# pid_driver.net
KiCad netlist of a schematic drawn in EAGLE
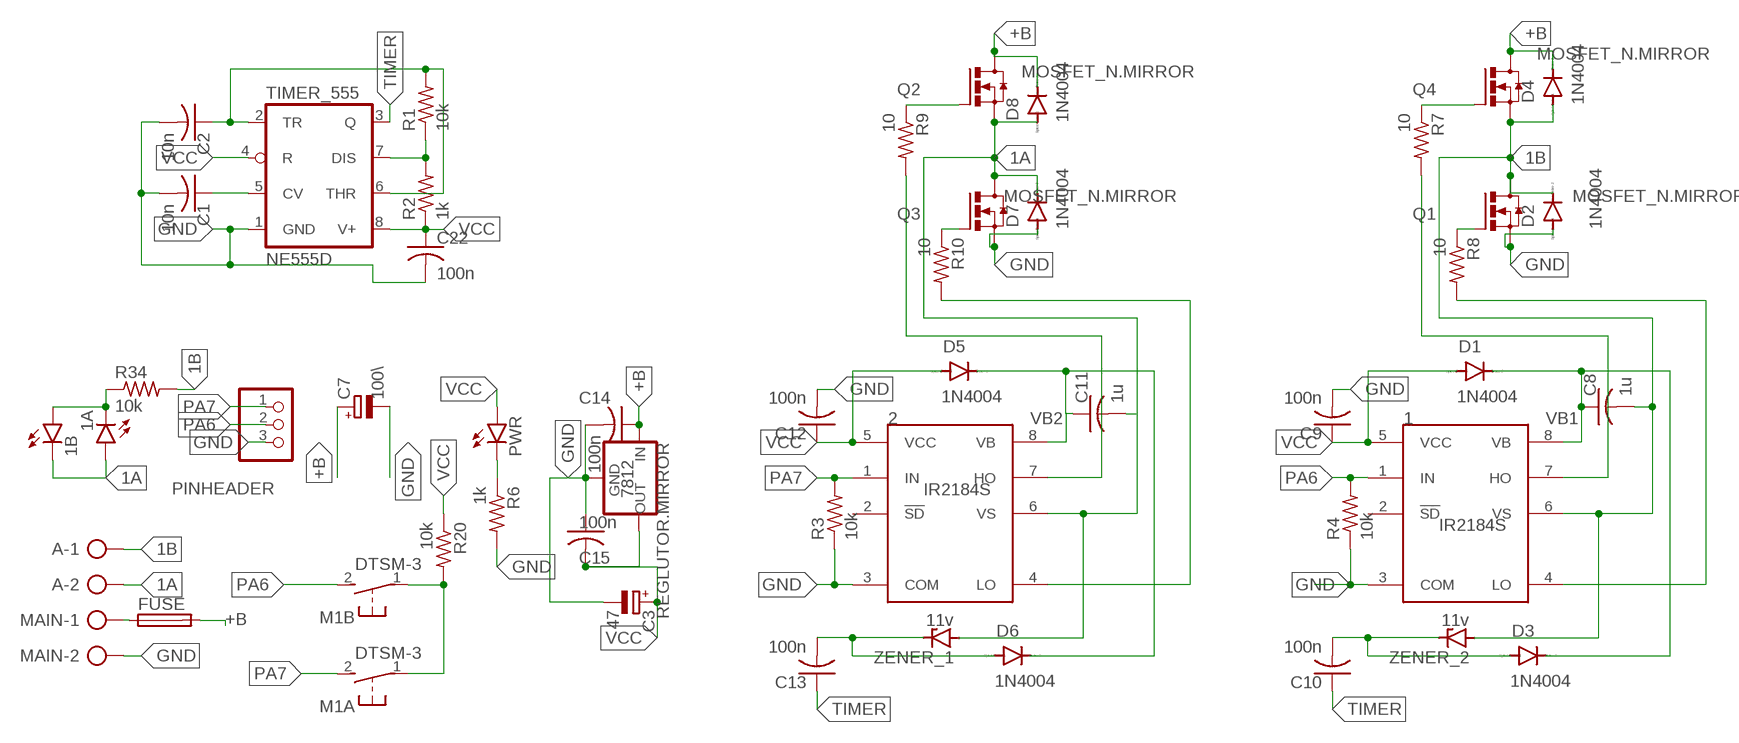
[diagram p0: schematic, sheet 1]
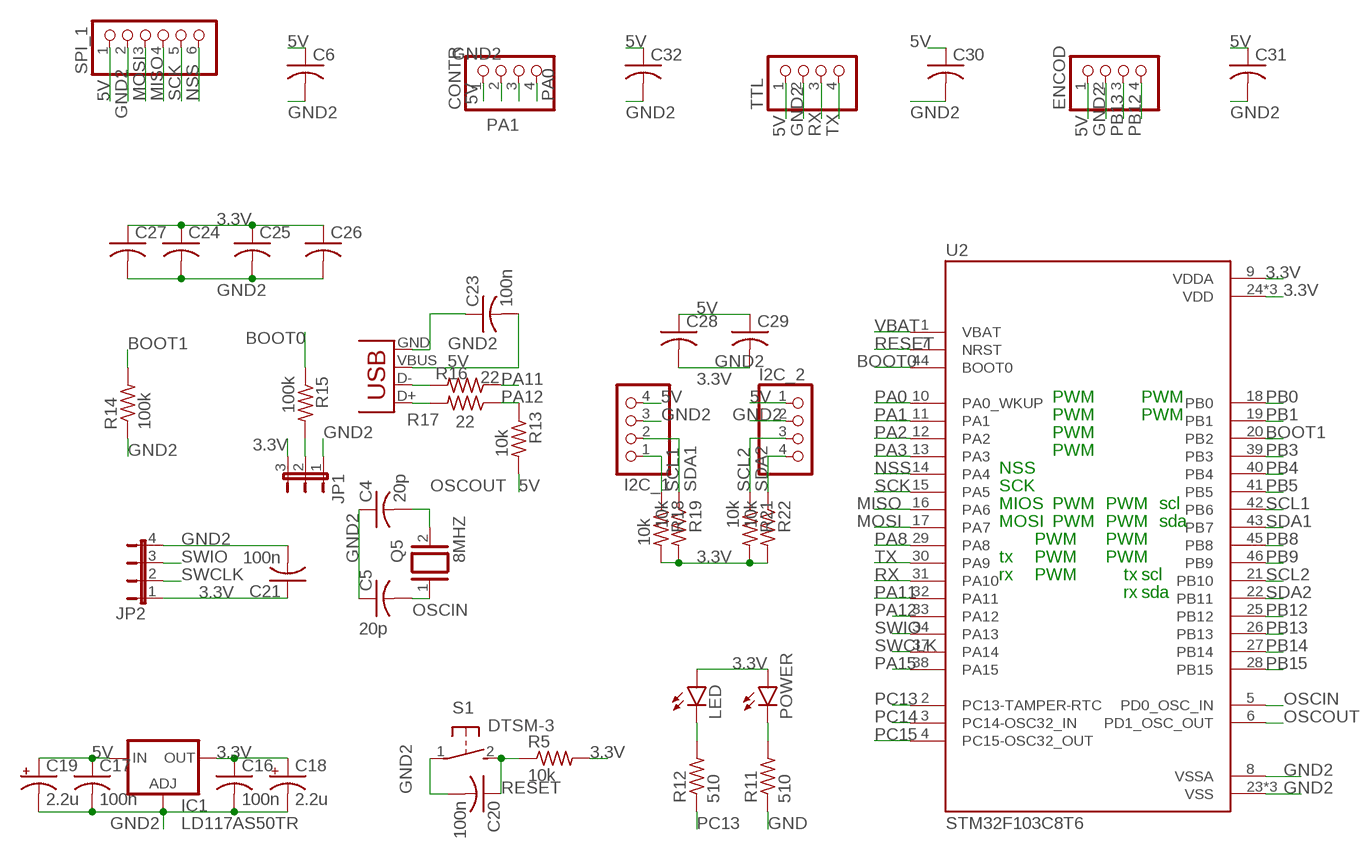
[diagram p1: schematic, sheet 2]

(export (version "E")
  (design (tool "Eeschema 10.0.6"))
  (components
    (comp (ref "1")
      (value "IR2184S")
      (footprint "eagle-import:SO08")
      (libsource (lib "eagle-import") (part "IR2184S"))
    )
    (comp (ref "1A")
      (value "LEDCHIPLED_1206")
      (footprint "eagle-import:CHIPLED_1206")
      (libsource (lib "eagle-import") (part "LEDCHIPLED_1206"))
    )
    (comp (ref "1B")
      (value "LEDCHIPLED_1206")
      (footprint "eagle-import:CHIPLED_1206")
      (libsource (lib "eagle-import") (part "LEDCHIPLED_1206"))
    )
    (comp (ref "2")
      (value "IR2184S")
      (footprint "eagle-import:SO08")
      (libsource (lib "eagle-import") (part "IR2184S"))
    )
    (comp (ref "7812")
      (value "REGLUTOR.MIRROR")
      (footprint "eagle-import:78XXL.MIRROR")
      (libsource (lib "eagle-import") (part "REGLUTOR.MIRROR"))
    )
    (comp (ref "A")
      (value "AK300/22")
      (footprint "eagle-import:XTALRR488W60L1090T465H350B")
      (libsource (lib "eagle-import") (part "AK300/22"))
    )
    (comp (ref "C1")
      (value "10n")
      (footprint "eagle-import:C1206K")
      (libsource (lib "eagle-import") (part "C-USC1206K"))
    )
    (comp (ref "C2")
      (value "10n")
      (footprint "eagle-import:C1206K")
      (libsource (lib "eagle-import") (part "C-USC1206K"))
    )
    (comp (ref "C3")
      (value "47")
      (footprint "eagle-import:E5-10,5")
      (libsource (lib "eagle-import") (part "CPOL-EUE5-10.5"))
    )
    (comp (ref "C7")
      (value "100\\")
      (footprint "eagle-import:E5-10,5")
      (libsource (lib "eagle-import") (part "CPOL-EUE5-10.5"))
    )
    (comp (ref "C8")
      (value "1u")
      (footprint "eagle-import:C1206K")
      (libsource (lib "eagle-import") (part "C-USC1206K"))
    )
    (comp (ref "C9")
      (value "100n")
      (footprint "eagle-import:C1206K")
      (libsource (lib "eagle-import") (part "C-USC1206K"))
    )
    (comp (ref "C10")
      (value "100n")
      (footprint "eagle-import:C1206K")
      (libsource (lib "eagle-import") (part "C-USC1206K"))
    )
    (comp (ref "C11")
      (value "1u")
      (footprint "eagle-import:C1206K")
      (libsource (lib "eagle-import") (part "C-USC1206K"))
    )
    (comp (ref "C12")
      (value "100n")
      (footprint "eagle-import:C1206K")
      (libsource (lib "eagle-import") (part "C-USC1206K"))
    )
    (comp (ref "C13")
      (value "100n")
      (footprint "eagle-import:C1206K")
      (libsource (lib "eagle-import") (part "C-USC1206K"))
    )
    (comp (ref "C14")
      (value "100n")
      (footprint "eagle-import:C1206K")
      (libsource (lib "eagle-import") (part "C-USC1206K"))
    )
    (comp (ref "C15")
      (value "100n")
      (footprint "eagle-import:C1206K")
      (libsource (lib "eagle-import") (part "C-USC1206K"))
    )
    (comp (ref "C22")
      (value "100n")
      (footprint "eagle-import:C1206K")
      (libsource (lib "eagle-import") (part "C-USC1206K"))
    )
    (comp (ref "D1")
      (value "1N4004")
      (footprint "eagle-import:DO41-10")
      (libsource (lib "eagle-import") (part "1N4004"))
    )
    (comp (ref "D2")
      (value "1N4004")
      (footprint "eagle-import:DO41-10")
      (libsource (lib "eagle-import") (part "1N4004"))
    )
    (comp (ref "D3")
      (value "1N4004")
      (footprint "eagle-import:DO41-10")
      (libsource (lib "eagle-import") (part "1N4004"))
    )
    (comp (ref "D4")
      (value "1N4004")
      (footprint "eagle-import:DO41-10")
      (libsource (lib "eagle-import") (part "1N4004"))
    )
    (comp (ref "D5")
      (value "1N4004")
      (footprint "eagle-import:DO41-10")
      (libsource (lib "eagle-import") (part "1N4004"))
    )
    (comp (ref "D6")
      (value "1N4004")
      (footprint "eagle-import:DO41-10")
      (libsource (lib "eagle-import") (part "1N4004"))
    )
    (comp (ref "D7")
      (value "1N4004")
      (footprint "eagle-import:DO41-10")
      (libsource (lib "eagle-import") (part "1N4004"))
    )
    (comp (ref "D8")
      (value "1N4004")
      (footprint "eagle-import:DO41-10")
      (libsource (lib "eagle-import") (part "1N4004"))
    )
    (comp (ref "FUSE")
      (value "FUSE_HOLDER")
      (footprint "eagle-import:SH22,5A")
      (libsource (lib "eagle-import") (part "FUSE_HOLDER"))
    )
    (comp (ref "M1A")
      (value "DTSM-3")
      (footprint "eagle-import:DTSM-3")
      (libsource (lib "eagle-import") (part "DTSM-3"))
    )
    (comp (ref "M1B")
      (value "DTSM-3")
      (footprint "eagle-import:DTSM-3")
      (libsource (lib "eagle-import") (part "DTSM-3"))
    )
    (comp (ref "MAIN")
      (value "AK300/22")
      (footprint "eagle-import:XTALRR488W60L1090T465H350B")
      (libsource (lib "eagle-import") (part "AK300/22"))
    )
    (comp (ref "PINHEADER")
      (value "PINHD-1X3")
      (footprint "eagle-import:1X03")
      (libsource (lib "eagle-import") (part "PINHD-1X3"))
    )
    (comp (ref "PWR")
      (value "LEDCHIPLED_1206")
      (footprint "eagle-import:CHIPLED_1206")
      (libsource (lib "eagle-import") (part "LEDCHIPLED_1206"))
    )
    (comp (ref "Q1")
      (value "MOSFET_N.MIRROR")
      (footprint "eagle-import:TO220.MIRROR")
      (libsource (lib "eagle-import") (part "MOSFET_N.MIRROR"))
    )
    (comp (ref "Q2")
      (value "MOSFET_N.MIRROR")
      (footprint "eagle-import:TO220.MIRROR")
      (libsource (lib "eagle-import") (part "MOSFET_N.MIRROR"))
    )
    (comp (ref "Q3")
      (value "MOSFET_N.MIRROR")
      (footprint "eagle-import:TO220.MIRROR")
      (libsource (lib "eagle-import") (part "MOSFET_N.MIRROR"))
    )
    (comp (ref "Q4")
      (value "MOSFET_N.MIRROR")
      (footprint "eagle-import:TO220.MIRROR")
      (libsource (lib "eagle-import") (part "MOSFET_N.MIRROR"))
    )
    (comp (ref "R1")
      (value "10k")
      (footprint "eagle-import:M1206")
      (libsource (lib "eagle-import") (part "R-US_M1206"))
    )
    (comp (ref "R2")
      (value "1k")
      (footprint "eagle-import:M1206")
      (libsource (lib "eagle-import") (part "R-US_M1206"))
    )
    (comp (ref "R3")
      (value "10k")
      (footprint "eagle-import:M1206")
      (libsource (lib "eagle-import") (part "R-US_M1206"))
    )
    (comp (ref "R4")
      (value "10k")
      (footprint "eagle-import:M1206")
      (libsource (lib "eagle-import") (part "R-US_M1206"))
    )
    (comp (ref "R6")
      (value "1k")
      (footprint "eagle-import:M1206")
      (libsource (lib "eagle-import") (part "R-US_M1206"))
    )
    (comp (ref "R7")
      (value "10")
      (footprint "eagle-import:M1206")
      (libsource (lib "eagle-import") (part "R-US_M1206"))
    )
    (comp (ref "R8")
      (value "10")
      (footprint "eagle-import:M1206")
      (libsource (lib "eagle-import") (part "R-US_M1206"))
    )
    (comp (ref "R9")
      (value "10")
      (footprint "eagle-import:M1206")
      (libsource (lib "eagle-import") (part "R-US_M1206"))
    )
    (comp (ref "R10")
      (value "10")
      (footprint "eagle-import:M1206")
      (libsource (lib "eagle-import") (part "R-US_M1206"))
    )
    (comp (ref "R20")
      (value "10k")
      (footprint "eagle-import:M1206")
      (libsource (lib "eagle-import") (part "R-US_M1206"))
    )
    (comp (ref "R34")
      (value "10k")
      (footprint "eagle-import:M1206")
      (libsource (lib "eagle-import") (part "R-US_M1206"))
    )
    (comp (ref "TIMER_555")
      (value "NE555D")
      (footprint "eagle-import:SO08")
      (libsource (lib "eagle-import") (part "555DNE"))
    )
    (comp (ref "ZENER_1")
      (value "11v")
      (footprint "eagle-import:SOD81")
      (libsource (lib "eagle-import") (part "BZD23"))
    )
    (comp (ref "ZENER_2")
      (value "11v")
      (footprint "eagle-import:SOD81")
      (libsource (lib "eagle-import") (part "BZD23"))
    )
    (comp (ref "C4")
      (value "20p")
      (footprint "eagle-import:C1206")
      (libsource (lib "eagle-import") (part "C-USC1206"))
    )
    (comp (ref "C5")
      (value "20p")
      (footprint "eagle-import:C1206")
      (libsource (lib "eagle-import") (part "C-USC1206"))
    )
    (comp (ref "C6")
      (value "C-USC1206")
      (footprint "eagle-import:C1206")
      (libsource (lib "eagle-import") (part "C-USC1206"))
    )
    (comp (ref "C16")
      (value "100n")
      (footprint "eagle-import:C1206")
      (libsource (lib "eagle-import") (part "C-USC1206"))
    )
    (comp (ref "C17")
      (value "100n")
      (footprint "eagle-import:C1206")
      (libsource (lib "eagle-import") (part "C-USC1206"))
    )
    (comp (ref "C18")
      (value "2.2u")
      (footprint "eagle-import:E2-5")
      (libsource (lib "eagle-import") (part "CPOL-USE2-5"))
    )
    (comp (ref "C19")
      (value "2.2u")
      (footprint "eagle-import:E2-5")
      (libsource (lib "eagle-import") (part "CPOL-USE2-5"))
    )
    (comp (ref "C20")
      (value "100n")
      (footprint "eagle-import:C1206")
      (libsource (lib "eagle-import") (part "C-USC1206"))
    )
    (comp (ref "C21")
      (value "100n")
      (footprint "eagle-import:C1206")
      (libsource (lib "eagle-import") (part "C-USC1206"))
    )
    (comp (ref "C23")
      (value "100n")
      (footprint "eagle-import:C1206")
      (libsource (lib "eagle-import") (part "C-USC1206"))
    )
    (comp (ref "C24")
      (value "C-USC1206")
      (footprint "eagle-import:C1206")
      (libsource (lib "eagle-import") (part "C-USC1206"))
    )
    (comp (ref "C25")
      (value "C-USC1206")
      (footprint "eagle-import:C1206")
      (libsource (lib "eagle-import") (part "C-USC1206"))
    )
    (comp (ref "C26")
      (value "C-USC1206")
      (footprint "eagle-import:C1206")
      (libsource (lib "eagle-import") (part "C-USC1206"))
    )
    (comp (ref "C27")
      (value "C-USC1206")
      (footprint "eagle-import:C1206")
      (libsource (lib "eagle-import") (part "C-USC1206"))
    )
    (comp (ref "C28")
      (value "C-USC1206")
      (footprint "eagle-import:C1206")
      (libsource (lib "eagle-import") (part "C-USC1206"))
    )
    (comp (ref "C29")
      (value "C-USC1206")
      (footprint "eagle-import:C1206")
      (libsource (lib "eagle-import") (part "C-USC1206"))
    )
    (comp (ref "C30")
      (value "C-USC1206")
      (footprint "eagle-import:C1206")
      (libsource (lib "eagle-import") (part "C-USC1206"))
    )
    (comp (ref "C31")
      (value "C-USC1206")
      (footprint "eagle-import:C1206")
      (libsource (lib "eagle-import") (part "C-USC1206"))
    )
    (comp (ref "C32")
      (value "C-USC1206")
      (footprint "eagle-import:C1206")
      (libsource (lib "eagle-import") (part "C-USC1206"))
    )
    (comp (ref "CONTR")
      (value "PINHD-1X4")
      (footprint "eagle-import:1X04")
      (libsource (lib "eagle-import") (part "PINHD-1X4"))
    )
    (comp (ref "ENCOD")
      (value "PINHD-1X4")
      (footprint "eagle-import:1X04")
      (libsource (lib "eagle-import") (part "PINHD-1X4"))
    )
    (comp (ref "I2C_1")
      (value "PINHD-1X4")
      (footprint "eagle-import:1X04")
      (libsource (lib "eagle-import") (part "pinhead_325_PINHD-1X4"))
    )
    (comp (ref "I2C_2")
      (value "PINHD-1X4")
      (footprint "eagle-import:1X04")
      (libsource (lib "eagle-import") (part "pinhead_325_PINHD-1X4"))
    )
    (comp (ref "IC1")
      (value "LD117AS50TR")
      (footprint "eagle-import:SOT223")
      (libsource (lib "eagle-import") (part "LD117A?S50TR"))
    )
    (comp (ref "JP1")
      (value "JP2E")
      (footprint "eagle-import:JP2")
      (libsource (lib "eagle-import") (part "JP2E"))
    )
    (comp (ref "JP2")
      (value "JP4E")
      (footprint "eagle-import:JP4")
      (libsource (lib "eagle-import") (part "JP4E"))
    )
    (comp (ref "LED")
      (value "LEDCHIPLED_1206")
      (footprint "eagle-import:CHIPLED_1206")
      (libsource (lib "eagle-import") (part "LEDCHIPLED_1206"))
    )
    (comp (ref "POWER")
      (value "LEDCHIPLED_1206")
      (footprint "eagle-import:CHIPLED_1206")
      (libsource (lib "eagle-import") (part "LEDCHIPLED_1206"))
    )
    (comp (ref "Q5")
      (value "8MHZ")
      (footprint "eagle-import:QS")
      (libsource (lib "eagle-import") (part "XTAL/S"))
    )
    (comp (ref "R5")
      (value "10k")
      (footprint "eagle-import:R1206")
      (libsource (lib "eagle-import") (part "R-US_R1206"))
    )
    (comp (ref "R11")
      (value "510")
      (footprint "eagle-import:R1206")
      (libsource (lib "eagle-import") (part "R-US_R1206"))
    )
    (comp (ref "R12")
      (value "510")
      (footprint "eagle-import:R1206")
      (libsource (lib "eagle-import") (part "R-US_R1206"))
    )
    (comp (ref "R13")
      (value "10k")
      (footprint "eagle-import:R1206")
      (libsource (lib "eagle-import") (part "R-US_R1206"))
    )
    (comp (ref "R14")
      (value "100k")
      (footprint "eagle-import:R1206")
      (libsource (lib "eagle-import") (part "R-US_R1206"))
    )
    (comp (ref "R15")
      (value "100k")
      (footprint "eagle-import:R1206")
      (libsource (lib "eagle-import") (part "R-US_R1206"))
    )
    (comp (ref "R16")
      (value "22")
      (footprint "eagle-import:R1206")
      (libsource (lib "eagle-import") (part "R-US_R1206"))
    )
    (comp (ref "R17")
      (value "22")
      (footprint "eagle-import:R1206")
      (libsource (lib "eagle-import") (part "R-US_R1206"))
    )
    (comp (ref "R18")
      (value "10k")
      (footprint "eagle-import:R1206")
      (libsource (lib "eagle-import") (part "R-US_R1206"))
    )
    (comp (ref "R19")
      (value "10k")
      (footprint "eagle-import:R1206")
      (libsource (lib "eagle-import") (part "R-US_R1206"))
    )
    (comp (ref "R21")
      (value "10k")
      (footprint "eagle-import:R1206")
      (libsource (lib "eagle-import") (part "R-US_R1206"))
    )
    (comp (ref "R22")
      (value "10k")
      (footprint "eagle-import:R1206")
      (libsource (lib "eagle-import") (part "R-US_R1206"))
    )
    (comp (ref "S1")
      (value "DTSM-3")
      (footprint "eagle-import:DTSM-3")
      (libsource (lib "eagle-import") (part "DTSM-3"))
    )
    (comp (ref "SPI_1")
      (value "PINHD-1X6")
      (footprint "eagle-import:1X06")
      (libsource (lib "eagle-import") (part "PINHD-1X6"))
    )
    (comp (ref "TTL")
      (value "PINHD-1X4")
      (footprint "eagle-import:1X04")
      (libsource (lib "eagle-import") (part "PINHD-1X4"))
    )
    (comp (ref "U2")
      (value "STM32F103C8T6")
      (footprint "eagle-import:QFP50P900X900X160-48N")
      (fields (field (name "MF") "STMicroelectronics"))
      (libsource (lib "eagle-import") (part "STM32F103C8T6"))
    )
    (comp (ref "X1")
      (value "USB-MB-S")
      (footprint "eagle-import:USB-MB-S")
      (libsource (lib "eagle-import") (part "USB-MB-S"))
    )
  )
  (nets
    (net (code "1") (name "+B") (class "Default")
      (node (ref "7812") (pin "IN") (pinfunction "IN_IN") (pintype "input"))
      (node (ref "C14") (pin "1") (pinfunction "1_1") (pintype "passive"))
      (node (ref "C7") (pin "+") (pinfunction "+_+") (pintype "passive"))
      (node (ref "D4") (pin "C") (pinfunction "C_C") (pintype "passive"))
      (node (ref "D8") (pin "C") (pinfunction "C_C") (pintype "passive"))
      (node (ref "FUSE") (pin "2") (pinfunction "2_2") (pintype "passive"))
      (node (ref "Q2") (pin "D") (pinfunction "D_D") (pintype "passive"))
      (node (ref "Q4") (pin "D") (pinfunction "D_D") (pintype "passive"))
    )
    (net (code "2") (name "1A") (class "Default")
      (node (ref "1A") (pin "A") (pinfunction "A_A") (pintype "passive"))
      (node (ref "1B") (pin "C") (pinfunction "C_C") (pintype "passive"))
      (node (ref "2") (pin "6") (pinfunction "VS_6") (pintype "power_in"))
      (node (ref "A") (pin "2") (pinfunction "KL_2") (pintype "passive"))
      (node (ref "C11") (pin "2") (pinfunction "2_2") (pintype "passive"))
      (node (ref "D7") (pin "C") (pinfunction "C_C") (pintype "passive"))
      (node (ref "D8") (pin "A") (pinfunction "A_A") (pintype "passive"))
      (node (ref "Q2") (pin "S") (pinfunction "S_S") (pintype "passive"))
      (node (ref "Q3") (pin "D") (pinfunction "D_D") (pintype "passive"))
      (node (ref "ZENER_1") (pin "A") (pinfunction "A_A") (pintype "passive"))
    )
    (net (code "3") (name "1B") (class "Default")
      (node (ref "1") (pin "6") (pinfunction "VS_6") (pintype "power_in"))
      (node (ref "A") (pin "1") (pinfunction "KL_1") (pintype "passive"))
      (node (ref "C8") (pin "2") (pinfunction "2_2") (pintype "passive"))
      (node (ref "D2") (pin "C") (pinfunction "C_C") (pintype "passive"))
      (node (ref "D4") (pin "A") (pinfunction "A_A") (pintype "passive"))
      (node (ref "Q1") (pin "D") (pinfunction "D_D") (pintype "passive"))
      (node (ref "Q4") (pin "S") (pinfunction "S_S") (pintype "passive"))
      (node (ref "R34") (pin "2") (pinfunction "2_2") (pintype "passive"))
      (node (ref "ZENER_2") (pin "A") (pinfunction "A_A") (pintype "passive"))
    )
    (net (code "4") (name "3.3V") (class "Default")
      (node (ref "C16") (pin "1") (pinfunction "1_1") (pintype "passive"))
      (node (ref "C18") (pin "+") (pinfunction "+_+") (pintype "passive"))
      (node (ref "C21") (pin "1") (pinfunction "1_1") (pintype "passive"))
      (node (ref "C24") (pin "1") (pinfunction "1_1") (pintype "passive"))
      (node (ref "C25") (pin "1") (pinfunction "1_1") (pintype "passive"))
      (node (ref "C26") (pin "1") (pinfunction "1_1") (pintype "passive"))
      (node (ref "C27") (pin "1") (pinfunction "1_1") (pintype "passive"))
      (node (ref "IC1") (pin "4") (pinfunction "OUT_4") (pintype "passive"))
      (node (ref "JP1") (pin "3") (pinfunction "3_3") (pintype "passive"))
      (node (ref "JP2") (pin "1") (pinfunction "1_1") (pintype "passive"))
      (node (ref "LED") (pin "A") (pinfunction "A_A") (pintype "passive"))
      (node (ref "POWER") (pin "A") (pinfunction "A_A") (pintype "passive"))
      (node (ref "R18") (pin "2") (pinfunction "2_2") (pintype "passive"))
      (node (ref "R19") (pin "2") (pinfunction "2_2") (pintype "passive"))
      (node (ref "R21") (pin "2") (pinfunction "2_2") (pintype "passive"))
      (node (ref "R22") (pin "2") (pinfunction "2_2") (pintype "passive"))
      (node (ref "R5") (pin "2") (pinfunction "2_2") (pintype "passive"))
      (node (ref "U2") (pin "24") (pinfunction "VDD_24") (pintype "power_in"))
      (node (ref "U2") (pin "36") (pinfunction "VDD_36") (pintype "power_in"))
      (node (ref "U2") (pin "48") (pinfunction "VDD_48") (pintype "power_in"))
      (node (ref "U2") (pin "9") (pinfunction "VDDA_9") (pintype "power_in"))
    )
    (net (code "5") (name "5V") (class "Default")
      (node (ref "C17") (pin "1") (pinfunction "1_1") (pintype "passive"))
      (node (ref "C19") (pin "+") (pinfunction "+_+") (pintype "passive"))
      (node (ref "C23") (pin "2") (pinfunction "2_2") (pintype "passive"))
      (node (ref "C28") (pin "1") (pinfunction "1_1") (pintype "passive"))
      (node (ref "C29") (pin "1") (pinfunction "1_1") (pintype "passive"))
      (node (ref "C30") (pin "1") (pinfunction "1_1") (pintype "passive"))
      (node (ref "C31") (pin "1") (pinfunction "1_1") (pintype "passive"))
      (node (ref "C32") (pin "1") (pinfunction "1_1") (pintype "passive"))
      (node (ref "C6") (pin "1") (pinfunction "1_1") (pintype "passive"))
      (node (ref "CONTR") (pin "1") (pinfunction "1_1") (pintype "passive"))
      (node (ref "ENCOD") (pin "1") (pinfunction "1_1") (pintype "passive"))
      (node (ref "I2C_1") (pin "4") (pinfunction "4_4") (pintype "passive"))
      (node (ref "I2C_2") (pin "1") (pinfunction "1_1") (pintype "passive"))
      (node (ref "IC1") (pin "3") (pinfunction "IN_3") (pintype "input"))
      (node (ref "R13") (pin "2") (pinfunction "2_2") (pintype "passive"))
      (node (ref "SPI_1") (pin "1") (pinfunction "1_1") (pintype "passive"))
      (node (ref "TTL") (pin "1") (pinfunction "1_1") (pintype "passive"))
      (node (ref "X1") (pin "VBUS") (pinfunction "VBUS_VBUS") (pintype "bidirectional"))
    )
    (net (code "6") (name "BOOT0") (class "Default")
      (node (ref "R15") (pin "1") (pinfunction "1_1") (pintype "passive"))
      (node (ref "U2") (pin "44") (pinfunction "BOOT0_44") (pintype "input"))
    )
    (net (code "7") (name "BOOT1") (class "Default")
      (node (ref "R14") (pin "2") (pinfunction "2_2") (pintype "passive"))
      (node (ref "U2") (pin "20") (pinfunction "PB2_20") (pintype "bidirectional"))
    )
    (net (code "8") (name "GND") (class "Default")
      (node (ref "1") (pin "3") (pinfunction "COM_3") (pintype "power_in"))
      (node (ref "2") (pin "3") (pinfunction "COM_3") (pintype "power_in"))
      (node (ref "7812") (pin "GND") (pinfunction "GND_GND") (pintype "input"))
      (node (ref "C1") (pin "2") (pinfunction "2_2") (pintype "passive"))
      (node (ref "C12") (pin "2") (pinfunction "2_2") (pintype "passive"))
      (node (ref "C14") (pin "2") (pinfunction "2_2") (pintype "passive"))
      (node (ref "C15") (pin "1") (pinfunction "1_1") (pintype "passive"))
      (node (ref "C2") (pin "2") (pinfunction "2_2") (pintype "passive"))
      (node (ref "C22") (pin "2") (pinfunction "2_2") (pintype "passive"))
      (node (ref "C3") (pin "-") (pinfunction "-_-") (pintype "passive"))
      (node (ref "C7") (pin "-") (pinfunction "-_-") (pintype "passive"))
      (node (ref "C9") (pin "2") (pinfunction "2_2") (pintype "passive"))
      (node (ref "D2") (pin "A") (pinfunction "A_A") (pintype "passive"))
      (node (ref "D7") (pin "A") (pinfunction "A_A") (pintype "passive"))
      (node (ref "MAIN") (pin "2") (pinfunction "KL_2") (pintype "passive"))
      (node (ref "PINHEADER") (pin "3") (pinfunction "3_3") (pintype "passive"))
      (node (ref "Q1") (pin "S") (pinfunction "S_S") (pintype "passive"))
      (node (ref "Q3") (pin "S") (pinfunction "S_S") (pintype "passive"))
      (node (ref "R11") (pin "1") (pinfunction "1_1") (pintype "passive"))
      (node (ref "R3") (pin "1") (pinfunction "1_1") (pintype "passive"))
      (node (ref "R4") (pin "1") (pinfunction "1_1") (pintype "passive"))
      (node (ref "R6") (pin "2") (pinfunction "2_2") (pintype "passive"))
      (node (ref "TIMER_555") (pin "1") (pinfunction "GND_1") (pintype "power_in"))
    )
    (net (code "9") (name "GND2") (class "Default")
      (node (ref "C16") (pin "2") (pinfunction "2_2") (pintype "passive"))
      (node (ref "C17") (pin "2") (pinfunction "2_2") (pintype "passive"))
      (node (ref "C18") (pin "-") (pinfunction "-_-") (pintype "passive"))
      (node (ref "C19") (pin "-") (pinfunction "-_-") (pintype "passive"))
      (node (ref "C20") (pin "2") (pinfunction "2_2") (pintype "passive"))
      (node (ref "C21") (pin "2") (pinfunction "2_2") (pintype "passive"))
      (node (ref "C23") (pin "1") (pinfunction "1_1") (pintype "passive"))
      (node (ref "C24") (pin "2") (pinfunction "2_2") (pintype "passive"))
      (node (ref "C25") (pin "2") (pinfunction "2_2") (pintype "passive"))
      (node (ref "C26") (pin "2") (pinfunction "2_2") (pintype "passive"))
      (node (ref "C27") (pin "2") (pinfunction "2_2") (pintype "passive"))
      (node (ref "C28") (pin "2") (pinfunction "2_2") (pintype "passive"))
      (node (ref "C29") (pin "2") (pinfunction "2_2") (pintype "passive"))
      (node (ref "C30") (pin "2") (pinfunction "2_2") (pintype "passive"))
      (node (ref "C31") (pin "2") (pinfunction "2_2") (pintype "passive"))
      (node (ref "C32") (pin "2") (pinfunction "2_2") (pintype "passive"))
      (node (ref "C4") (pin "1") (pinfunction "1_1") (pintype "passive"))
      (node (ref "C5") (pin "1") (pinfunction "1_1") (pintype "passive"))
      (node (ref "C6") (pin "2") (pinfunction "2_2") (pintype "passive"))
      (node (ref "CONTR") (pin "2") (pinfunction "2_2") (pintype "passive"))
      (node (ref "ENCOD") (pin "2") (pinfunction "2_2") (pintype "passive"))
      (node (ref "I2C_1") (pin "3") (pinfunction "3_3") (pintype "passive"))
      (node (ref "I2C_2") (pin "2") (pinfunction "2_2") (pintype "passive"))
      (node (ref "IC1") (pin "1") (pinfunction "ADJ_1") (pintype "input"))
      (node (ref "JP1") (pin "1") (pinfunction "1_1") (pintype "passive"))
      (node (ref "JP2") (pin "4") (pinfunction "4_4") (pintype "passive"))
      (node (ref "R14") (pin "1") (pinfunction "1_1") (pintype "passive"))
      (node (ref "S1") (pin "1") (pinfunction "1_1") (pintype "passive"))
      (node (ref "SPI_1") (pin "2") (pinfunction "2_2") (pintype "passive"))
      (node (ref "TTL") (pin "2") (pinfunction "2_2") (pintype "passive"))
      (node (ref "U2") (pin "23") (pinfunction "VSS_23") (pintype "power_in"))
      (node (ref "U2") (pin "35") (pinfunction "VSS_35") (pintype "power_in"))
      (node (ref "U2") (pin "47") (pinfunction "VSS_47") (pintype "power_in"))
      (node (ref "U2") (pin "8") (pinfunction "VSSA_8") (pintype "power_in"))
      (node (ref "X1") (pin "GND") (pinfunction "GND_GND") (pintype "bidirectional"))
    )
    (net (code "10") (name "MISO") (class "Default")
      (node (ref "SPI_1") (pin "4") (pinfunction "4_4") (pintype "passive"))
      (node (ref "U2") (pin "16") (pinfunction "PA6_16") (pintype "bidirectional"))
    )
    (net (code "11") (name "MOSI") (class "Default")
      (node (ref "SPI_1") (pin "3") (pinfunction "3_3") (pintype "passive"))
      (node (ref "U2") (pin "17") (pinfunction "PA7_17") (pintype "bidirectional"))
    )
    (net (code "12") (name "NSS") (class "Default")
      (node (ref "SPI_1") (pin "6") (pinfunction "6_6") (pintype "passive"))
      (node (ref "U2") (pin "14") (pinfunction "PA4_14") (pintype "bidirectional"))
    )
    (net (code "13") (name "Net-(1-HO)") (class "Default")
      (node (ref "1") (pin "7") (pinfunction "HO_7") (pintype "output"))
      (node (ref "R7") (pin "2") (pinfunction "2_2") (pintype "passive"))
    )
    (net (code "14") (name "Net-(1-LO)") (class "Default")
      (node (ref "1") (pin "4") (pinfunction "LO_4") (pintype "output"))
      (node (ref "R8") (pin "2") (pinfunction "2_2") (pintype "passive"))
    )
    (net (code "15") (name "Net-(1A-PadC)") (class "Default")
      (node (ref "1A") (pin "C") (pinfunction "C_C") (pintype "passive"))
      (node (ref "1B") (pin "A") (pinfunction "A_A") (pintype "passive"))
      (node (ref "R34") (pin "1") (pinfunction "1_1") (pintype "passive"))
    )
    (net (code "16") (name "Net-(2-HO)") (class "Default")
      (node (ref "2") (pin "7") (pinfunction "HO_7") (pintype "output"))
      (node (ref "R9") (pin "2") (pinfunction "2_2") (pintype "passive"))
    )
    (net (code "17") (name "Net-(2-LO)") (class "Default")
      (node (ref "2") (pin "4") (pinfunction "LO_4") (pintype "output"))
      (node (ref "R10") (pin "2") (pinfunction "2_2") (pintype "passive"))
    )
    (net (code "18") (name "Net-(C10-Pad2)") (class "Default")
      (node (ref "C10") (pin "2") (pinfunction "2_2") (pintype "passive"))
      (node (ref "D3") (pin "A") (pinfunction "A_A") (pintype "passive"))
      (node (ref "ZENER_2") (pin "C") (pinfunction "C_C") (pintype "passive"))
    )
    (net (code "19") (name "Net-(C13-Pad2)") (class "Default")
      (node (ref "C13") (pin "2") (pinfunction "2_2") (pintype "passive"))
      (node (ref "D6") (pin "A") (pinfunction "A_A") (pintype "passive"))
      (node (ref "ZENER_1") (pin "C") (pinfunction "C_C") (pintype "passive"))
    )
    (net (code "20") (name "Net-(JP1-Pad2)") (class "Default")
      (node (ref "JP1") (pin "2") (pinfunction "2_2") (pintype "passive"))
      (node (ref "R15") (pin "2") (pinfunction "2_2") (pintype "passive"))
    )
    (net (code "21") (name "Net-(LED-PadC)") (class "Default")
      (node (ref "LED") (pin "C") (pinfunction "C_C") (pintype "passive"))
      (node (ref "R12") (pin "2") (pinfunction "2_2") (pintype "passive"))
    )
    (net (code "22") (name "Net-(M1A-Pad1)") (class "Default")
      (node (ref "M1A") (pin "1") (pinfunction "1_1") (pintype "passive"))
      (node (ref "M1B") (pin "1") (pinfunction "1_1") (pintype "passive"))
      (node (ref "R20") (pin "2") (pinfunction "2_2") (pintype "passive"))
    )
    (net (code "23") (name "Net-(MAINA-KL)") (class "Default")
      (node (ref "FUSE") (pin "1") (pinfunction "1_1") (pintype "passive"))
      (node (ref "MAIN") (pin "1") (pinfunction "KL_1") (pintype "passive"))
    )
    (net (code "24") (name "Net-(POWER-PadC)") (class "Default")
      (node (ref "POWER") (pin "C") (pinfunction "C_C") (pintype "passive"))
      (node (ref "R11") (pin "2") (pinfunction "2_2") (pintype "passive"))
    )
    (net (code "25") (name "Net-(PWR-PadC)") (class "Default")
      (node (ref "PWR") (pin "C") (pinfunction "C_C") (pintype "passive"))
      (node (ref "R6") (pin "1") (pinfunction "1_1") (pintype "passive"))
    )
    (net (code "26") (name "Net-(Q1-PadG)") (class "Default")
      (node (ref "Q1") (pin "G") (pinfunction "G_G") (pintype "passive"))
      (node (ref "R8") (pin "1") (pinfunction "1_1") (pintype "passive"))
    )
    (net (code "27") (name "Net-(Q2-PadG)") (class "Default")
      (node (ref "Q2") (pin "G") (pinfunction "G_G") (pintype "passive"))
      (node (ref "R9") (pin "1") (pinfunction "1_1") (pintype "passive"))
    )
    (net (code "28") (name "Net-(Q3-PadG)") (class "Default")
      (node (ref "Q3") (pin "G") (pinfunction "G_G") (pintype "passive"))
      (node (ref "R10") (pin "1") (pinfunction "1_1") (pintype "passive"))
    )
    (net (code "29") (name "Net-(Q4-PadG)") (class "Default")
      (node (ref "Q4") (pin "G") (pinfunction "G_G") (pintype "passive"))
      (node (ref "R7") (pin "1") (pinfunction "1_1") (pintype "passive"))
    )
    (net (code "30") (name "Net-(R16-Pad2)") (class "Default")
      (node (ref "R16") (pin "2") (pinfunction "2_2") (pintype "passive"))
      (node (ref "X1") (pin "D-") (pinfunction "D-_D-") (pintype "bidirectional"))
    )
    (net (code "31") (name "Net-(R17-Pad2)") (class "Default")
      (node (ref "R17") (pin "2") (pinfunction "2_2") (pintype "passive"))
      (node (ref "X1") (pin "D+") (pinfunction "D+_D+") (pintype "bidirectional"))
    )
    (net (code "32") (name "Net-(TIMER_555-CV)") (class "Default")
      (node (ref "C1") (pin "1") (pinfunction "1_1") (pintype "passive"))
      (node (ref "TIMER_555") (pin "5") (pinfunction "CV_5") (pintype "input"))
    )
    (net (code "33") (name "Net-(TIMER_555-DIS)") (class "Default")
      (node (ref "R1") (pin "1") (pinfunction "1_1") (pintype "passive"))
      (node (ref "R2") (pin "2") (pinfunction "2_2") (pintype "passive"))
      (node (ref "TIMER_555") (pin "7") (pinfunction "DIS_7") (pintype "input"))
    )
    (net (code "34") (name "Net-(TIMER_555-THR)") (class "Default")
      (node (ref "C2") (pin "1") (pinfunction "1_1") (pintype "passive"))
      (node (ref "R1") (pin "2") (pinfunction "2_2") (pintype "passive"))
      (node (ref "TIMER_555") (pin "2") (pinfunction "TR_2") (pintype "input"))
      (node (ref "TIMER_555") (pin "6") (pinfunction "THR_6") (pintype "input"))
    )
    (net (code "35") (name "OSCIN") (class "Default")
      (node (ref "C5") (pin "2") (pinfunction "2_2") (pintype "passive"))
      (node (ref "Q5") (pin "1") (pinfunction "1_1") (pintype "passive"))
      (node (ref "U2") (pin "5") (pinfunction "PD0_OSC_IN_5") (pintype "bidirectional"))
    )
    (net (code "36") (name "OSCOUT") (class "Default")
      (node (ref "C4") (pin "2") (pinfunction "2_2") (pintype "passive"))
      (node (ref "Q5") (pin "2") (pinfunction "2_2") (pintype "passive"))
      (node (ref "U2") (pin "6") (pinfunction "PD1_OSC_OUT_6") (pintype "bidirectional"))
    )
    (net (code "37") (name "PA0") (class "Default")
      (node (ref "CONTR") (pin "4") (pinfunction "4_4") (pintype "passive"))
      (node (ref "U2") (pin "10") (pinfunction "PA0_WKUP_10") (pintype "bidirectional"))
    )
    (net (code "38") (name "PA1") (class "Default")
      (node (ref "CONTR") (pin "3") (pinfunction "3_3") (pintype "passive"))
      (node (ref "U2") (pin "11") (pinfunction "PA1_11") (pintype "bidirectional"))
    )
    (net (code "39") (name "PA2") (class "Default")
      (node (ref "U2") (pin "12") (pinfunction "PA2_12") (pintype "bidirectional"))
    )
    (net (code "40") (name "PA3") (class "Default")
      (node (ref "U2") (pin "13") (pinfunction "PA3_13") (pintype "bidirectional"))
    )
    (net (code "41") (name "PA6") (class "Default")
      (node (ref "1") (pin "1") (pinfunction "IN_1") (pintype "input"))
      (node (ref "M1B") (pin "2") (pinfunction "2_2") (pintype "passive"))
      (node (ref "PINHEADER") (pin "2") (pinfunction "2_2") (pintype "passive"))
      (node (ref "R4") (pin "2") (pinfunction "2_2") (pintype "passive"))
    )
    (net (code "42") (name "PA7") (class "Default")
      (node (ref "2") (pin "1") (pinfunction "IN_1") (pintype "input"))
      (node (ref "M1A") (pin "2") (pinfunction "2_2") (pintype "passive"))
      (node (ref "PINHEADER") (pin "1") (pinfunction "1_1") (pintype "passive"))
      (node (ref "R3") (pin "2") (pinfunction "2_2") (pintype "passive"))
    )
    (net (code "43") (name "PA8") (class "Default")
      (node (ref "U2") (pin "29") (pinfunction "PA8_29") (pintype "bidirectional"))
    )
    (net (code "44") (name "PA11") (class "Default")
      (node (ref "R16") (pin "1") (pinfunction "1_1") (pintype "passive"))
      (node (ref "U2") (pin "32") (pinfunction "PA11_32") (pintype "bidirectional"))
    )
    (net (code "45") (name "PA12") (class "Default")
      (node (ref "R13") (pin "1") (pinfunction "1_1") (pintype "passive"))
      (node (ref "R17") (pin "1") (pinfunction "1_1") (pintype "passive"))
      (node (ref "U2") (pin "33") (pinfunction "PA12_33") (pintype "bidirectional"))
    )
    (net (code "46") (name "PA15") (class "Default")
      (node (ref "U2") (pin "38") (pinfunction "PA15_38") (pintype "bidirectional"))
    )
    (net (code "47") (name "PB0") (class "Default")
      (node (ref "U2") (pin "18") (pinfunction "PB0_18") (pintype "bidirectional"))
    )
    (net (code "48") (name "PB1") (class "Default")
      (node (ref "U2") (pin "19") (pinfunction "PB1_19") (pintype "bidirectional"))
    )
    (net (code "49") (name "PB3") (class "Default")
      (node (ref "U2") (pin "39") (pinfunction "PB3_39") (pintype "bidirectional"))
    )
    (net (code "50") (name "PB4") (class "Default")
      (node (ref "U2") (pin "40") (pinfunction "PB4_40") (pintype "bidirectional"))
    )
    (net (code "51") (name "PB5") (class "Default")
      (node (ref "U2") (pin "41") (pinfunction "PB5_41") (pintype "bidirectional"))
    )
    (net (code "52") (name "PB8") (class "Default")
      (node (ref "U2") (pin "45") (pinfunction "PB8_45") (pintype "bidirectional"))
    )
    (net (code "53") (name "PB9") (class "Default")
      (node (ref "U2") (pin "46") (pinfunction "PB9_46") (pintype "bidirectional"))
    )
    (net (code "54") (name "PB12") (class "Default")
      (node (ref "ENCOD") (pin "4") (pinfunction "4_4") (pintype "passive"))
      (node (ref "U2") (pin "25") (pinfunction "PB12_25") (pintype "bidirectional"))
    )
    (net (code "55") (name "PB13") (class "Default")
      (node (ref "ENCOD") (pin "3") (pinfunction "3_3") (pintype "passive"))
      (node (ref "U2") (pin "26") (pinfunction "PB13_26") (pintype "bidirectional"))
    )
    (net (code "56") (name "PB14") (class "Default")
      (node (ref "U2") (pin "27") (pinfunction "PB14_27") (pintype "bidirectional"))
    )
    (net (code "57") (name "PB15") (class "Default")
      (node (ref "U2") (pin "28") (pinfunction "PB15_28") (pintype "bidirectional"))
    )
    (net (code "58") (name "PC13") (class "Default")
      (node (ref "R12") (pin "1") (pinfunction "1_1") (pintype "passive"))
      (node (ref "U2") (pin "2") (pinfunction "PC13-TAMPER-RTC_2") (pintype "bidirectional"))
    )
    (net (code "59") (name "PC14") (class "Default")
      (node (ref "U2") (pin "3") (pinfunction "PC14-OSC32_IN_3") (pintype "bidirectional"))
    )
    (net (code "60") (name "PC15") (class "Default")
      (node (ref "U2") (pin "4") (pinfunction "PC15-OSC32_OUT_4") (pintype "bidirectional"))
    )
    (net (code "61") (name "RESET") (class "Default")
      (node (ref "C20") (pin "1") (pinfunction "1_1") (pintype "passive"))
      (node (ref "R5") (pin "1") (pinfunction "1_1") (pintype "passive"))
      (node (ref "S1") (pin "2") (pinfunction "2_2") (pintype "passive"))
      (node (ref "U2") (pin "7") (pinfunction "NRST_7") (pintype "input"))
    )
    (net (code "62") (name "RX") (class "Default")
      (node (ref "TTL") (pin "3") (pinfunction "3_3") (pintype "passive"))
      (node (ref "U2") (pin "31") (pinfunction "PA10_31") (pintype "bidirectional"))
    )
    (net (code "63") (name "SCK") (class "Default")
      (node (ref "SPI_1") (pin "5") (pinfunction "5_5") (pintype "passive"))
      (node (ref "U2") (pin "15") (pinfunction "PA5_15") (pintype "bidirectional"))
    )
    (net (code "64") (name "SCL1") (class "Default")
      (node (ref "I2C_1") (pin "1") (pinfunction "1_1") (pintype "passive"))
      (node (ref "R18") (pin "1") (pinfunction "1_1") (pintype "passive"))
      (node (ref "U2") (pin "42") (pinfunction "PB6_42") (pintype "bidirectional"))
    )
    (net (code "65") (name "SCL2") (class "Default")
      (node (ref "I2C_2") (pin "3") (pinfunction "3_3") (pintype "passive"))
      (node (ref "R21") (pin "1") (pinfunction "1_1") (pintype "passive"))
      (node (ref "U2") (pin "21") (pinfunction "PB10_21") (pintype "bidirectional"))
    )
    (net (code "66") (name "SDA1") (class "Default")
      (node (ref "I2C_1") (pin "2") (pinfunction "2_2") (pintype "passive"))
      (node (ref "R19") (pin "1") (pinfunction "1_1") (pintype "passive"))
      (node (ref "U2") (pin "43") (pinfunction "PB7_43") (pintype "bidirectional"))
    )
    (net (code "67") (name "SDA2") (class "Default")
      (node (ref "I2C_2") (pin "4") (pinfunction "4_4") (pintype "passive"))
      (node (ref "R22") (pin "1") (pinfunction "1_1") (pintype "passive"))
      (node (ref "U2") (pin "22") (pinfunction "PB11_22") (pintype "bidirectional"))
    )
    (net (code "68") (name "SWCLK") (class "Default")
      (node (ref "JP2") (pin "2") (pinfunction "2_2") (pintype "passive"))
      (node (ref "U2") (pin "37") (pinfunction "PA14_37") (pintype "bidirectional"))
    )
    (net (code "69") (name "SWIO") (class "Default")
      (node (ref "JP2") (pin "3") (pinfunction "3_3") (pintype "passive"))
      (node (ref "U2") (pin "34") (pinfunction "PA13_34") (pintype "bidirectional"))
    )
    (net (code "70") (name "TIMER") (class "Default")
      (node (ref "C10") (pin "1") (pinfunction "1_1") (pintype "passive"))
      (node (ref "C13") (pin "1") (pinfunction "1_1") (pintype "passive"))
      (node (ref "TIMER_555") (pin "3") (pinfunction "Q_3") (pintype "output"))
    )
    (net (code "71") (name "TX") (class "Default")
      (node (ref "TTL") (pin "4") (pinfunction "4_4") (pintype "passive"))
      (node (ref "U2") (pin "30") (pinfunction "PA9_30") (pintype "bidirectional"))
    )
    (net (code "72") (name "VB1") (class "Default")
      (node (ref "1") (pin "8") (pinfunction "VB_8") (pintype "power_in"))
      (node (ref "C8") (pin "1") (pinfunction "1_1") (pintype "passive"))
      (node (ref "D1") (pin "C") (pinfunction "C_C") (pintype "passive"))
      (node (ref "D3") (pin "C") (pinfunction "C_C") (pintype "passive"))
    )
    (net (code "73") (name "VB2") (class "Default")
      (node (ref "2") (pin "8") (pinfunction "VB_8") (pintype "power_in"))
      (node (ref "C11") (pin "1") (pinfunction "1_1") (pintype "passive"))
      (node (ref "D5") (pin "C") (pinfunction "C_C") (pintype "passive"))
      (node (ref "D6") (pin "C") (pinfunction "C_C") (pintype "passive"))
    )
    (net (code "74") (name "VBAT") (class "Default")
      (node (ref "U2") (pin "1") (pinfunction "VBAT_1") (pintype "bidirectional"))
    )
    (net (code "75") (name "VCC") (class "Default")
      (node (ref "1") (pin "5") (pinfunction "VCC_5") (pintype "power_in"))
      (node (ref "2") (pin "5") (pinfunction "VCC_5") (pintype "power_in"))
      (node (ref "7812") (pin "OUT") (pinfunction "OUT_OUT") (pintype "passive"))
      (node (ref "C12") (pin "1") (pinfunction "1_1") (pintype "passive"))
      (node (ref "C15") (pin "2") (pinfunction "2_2") (pintype "passive"))
      (node (ref "C22") (pin "1") (pinfunction "1_1") (pintype "passive"))
      (node (ref "C3") (pin "+") (pinfunction "+_+") (pintype "passive"))
      (node (ref "C9") (pin "1") (pinfunction "1_1") (pintype "passive"))
      (node (ref "D1") (pin "A") (pinfunction "A_A") (pintype "passive"))
      (node (ref "D5") (pin "A") (pinfunction "A_A") (pintype "passive"))
      (node (ref "PWR") (pin "A") (pinfunction "A_A") (pintype "passive"))
      (node (ref "R2") (pin "1") (pinfunction "1_1") (pintype "passive"))
      (node (ref "R20") (pin "1") (pinfunction "1_1") (pintype "passive"))
      (node (ref "TIMER_555") (pin "4") (pinfunction "R_4") (pintype "input"))
      (node (ref "TIMER_555") (pin "8") (pinfunction "V+_8") (pintype "power_in"))
    )
    (net (code "76") (name "unconnected-(1-~{SD}-Pad2)") (class "Default")
      (node (ref "1") (pin "2") (pinfunction "~{SD}_2") (pintype "input"))
    )
    (net (code "77") (name "unconnected-(2-~{SD}-Pad2)") (class "Default")
      (node (ref "2") (pin "2") (pinfunction "~{SD}_2") (pintype "input"))
    )
  )
)
